# Sensor_v10.net
KiCad netlist of a schematic drawn in EAGLE
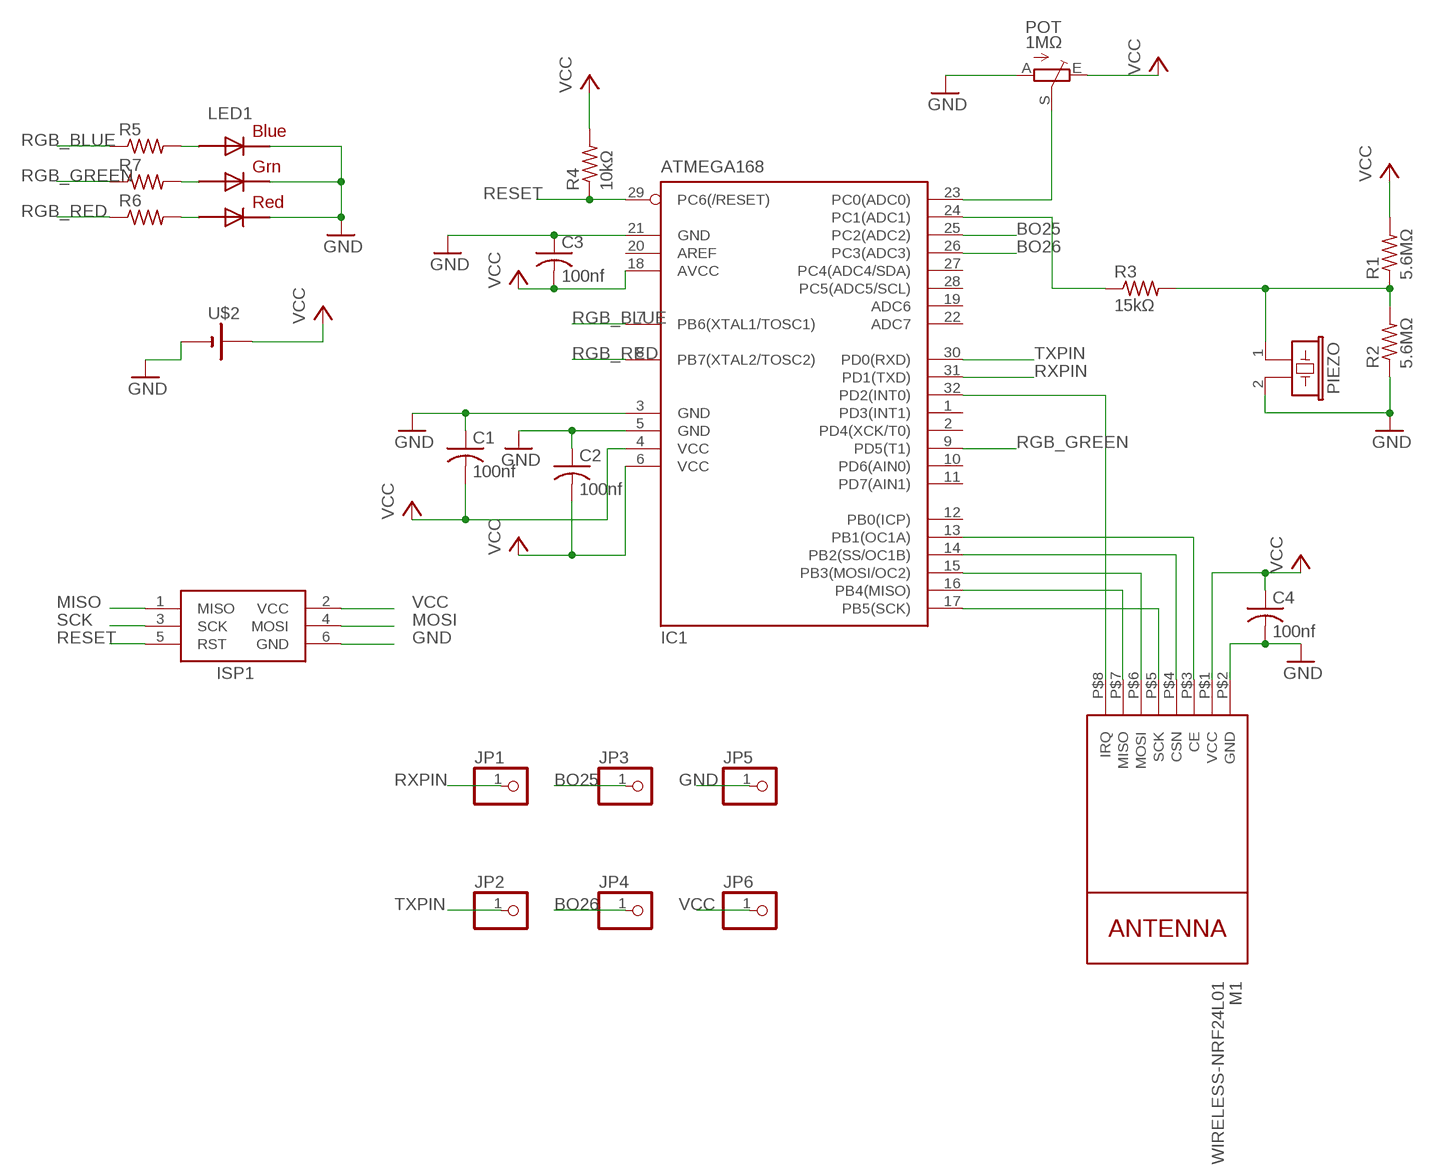
[diagram p0: schematic, sheet 1]

(export (version "E")
  (design (tool "Eeschema 10.0.6"))
  (components
    (comp (ref "C1")
      (value "100nf")
      (footprint "eagle-import:C0805")
      (libsource (lib "eagle-import") (part "resistor_C-USC0805"))
    )
    (comp (ref "C2")
      (value "100nf")
      (footprint "eagle-import:C0805")
      (libsource (lib "eagle-import") (part "C-USC0805"))
    )
    (comp (ref "C3")
      (value "100nf")
      (footprint "eagle-import:C0805")
      (libsource (lib "eagle-import") (part "resistor_C-USC0805"))
    )
    (comp (ref "C4")
      (value "100nf")
      (footprint "eagle-import:C0805")
      (libsource (lib "eagle-import") (part "C-USC0805"))
    )
    (comp (ref "IC1")
      (value "ATMEGA168")
      (footprint "eagle-import:TQFP32-08")
      (fields (field (name "MPN") "ATMEGA8-16AU"))
      (libsource (lib "eagle-import") (part "MEGA8-AI"))
    )
    (comp (ref "ISP1")
      (value "AVRISP-6")
      (footprint "eagle-import:AVRISP")
      (libsource (lib "eagle-import") (part "AVRISP-6"))
    )
    (comp (ref "JP1")
      (value "PINHD-1X1")
      (footprint "eagle-import:1X01")
      (libsource (lib "eagle-import") (part "PINHD-1X1"))
    )
    (comp (ref "JP2")
      (value "PINHD-1X1")
      (footprint "eagle-import:1X01")
      (libsource (lib "eagle-import") (part "PINHD-1X1"))
    )
    (comp (ref "JP3")
      (value "PINHD-1X1")
      (footprint "eagle-import:1X01")
      (libsource (lib "eagle-import") (part "PINHD-1X1"))
    )
    (comp (ref "JP4")
      (value "PINHD-1X1")
      (footprint "eagle-import:1X01")
      (libsource (lib "eagle-import") (part "PINHD-1X1"))
    )
    (comp (ref "JP5")
      (value "PINHD-1X1")
      (footprint "eagle-import:1X01")
      (libsource (lib "eagle-import") (part "PINHD-1X1"))
    )
    (comp (ref "JP6")
      (value "PINHD-1X1")
      (footprint "eagle-import:1X01")
      (libsource (lib "eagle-import") (part "PINHD-1X1"))
    )
    (comp (ref "LED1")
      (value "RGBLED5050")
      (footprint "eagle-import:RGBLED5050")
      (libsource (lib "eagle-import") (part "RGBLED5050"))
    )
    (comp (ref "M1")
      (value "WIRELESS-NRF24L01")
      (footprint "eagle-import:WIRELESS-NRF24L01")
      (libsource (lib "eagle-import") (part "WIRELESS-NRF24L01"))
    )
    (comp (ref "PIEZO")
      (value "EFBAA40D101")
      (footprint "eagle-import:EFBAA40D101")
      (libsource (lib "eagle-import") (part "EFB?AA40D101"))
    )
    (comp (ref "POT")
      (value "1MΩ")
      (footprint "eagle-import:CA6V")
      (libsource (lib "eagle-import") (part "TRIM_EU-CA6V"))
    )
    (comp (ref "R1")
      (value "5.6MΩ")
      (footprint "eagle-import:R0805")
      (libsource (lib "eagle-import") (part "R-US_R0805"))
    )
    (comp (ref "R2")
      (value "5.6MΩ")
      (footprint "eagle-import:R0805")
      (libsource (lib "eagle-import") (part "R-US_R0805"))
    )
    (comp (ref "R3")
      (value "15kΩ")
      (footprint "eagle-import:R0805")
      (libsource (lib "eagle-import") (part "R-US_R0805"))
    )
    (comp (ref "R4")
      (value "10kΩ")
      (footprint "eagle-import:R0805")
      (libsource (lib "eagle-import") (part "R-US_R0805"))
    )
    (comp (ref "R5")
      (value "R-US_R0805")
      (footprint "eagle-import:R0805")
      (libsource (lib "eagle-import") (part "R-US_R0805"))
    )
    (comp (ref "R6")
      (value "R-US_R0805")
      (footprint "eagle-import:R0805")
      (libsource (lib "eagle-import") (part "R-US_R0805"))
    )
    (comp (ref "R7")
      (value "R-US_R0805")
      (footprint "eagle-import:R0805")
      (libsource (lib "eagle-import") (part "R-US_R0805"))
    )
    (comp (ref "U$2")
      (value "CR2032SMT")
      (footprint "eagle-import:CR2032-SMD")
      (libsource (lib "eagle-import") (part "CR2032SMT"))
    )
  )
  (nets
    (net (code "1") (name "/BO25") (class "Default")
      (node (ref "IC1") (pin "25") (pinfunction "PC2(ADC2)_25") (pintype "bidirectional"))
      (node (ref "JP3") (pin "1") (pinfunction "1_1") (pintype "passive"))
    )
    (net (code "2") (name "/BO26") (class "Default")
      (node (ref "IC1") (pin "26") (pinfunction "PC3(ADC3)_26") (pintype "bidirectional"))
      (node (ref "JP4") (pin "1") (pinfunction "1_1") (pintype "passive"))
    )
    (net (code "3") (name "/MISO") (class "Default")
      (node (ref "IC1") (pin "16") (pinfunction "PB4(MISO)_16") (pintype "bidirectional"))
      (node (ref "ISP1") (pin "1") (pinfunction "MISO_1") (pintype "input"))
      (node (ref "M1") (pin "P$7") (pinfunction "MISO_P$7") (pintype "bidirectional"))
    )
    (net (code "4") (name "/MOSI") (class "Default")
      (node (ref "IC1") (pin "15") (pinfunction "PB3(MOSI/OC2)_15") (pintype "bidirectional"))
      (node (ref "ISP1") (pin "4") (pinfunction "MOSI_4") (pintype "output"))
      (node (ref "M1") (pin "P$6") (pinfunction "MOSI_P$6") (pintype "bidirectional"))
    )
    (net (code "5") (name "/RESET") (class "Default")
      (node (ref "IC1") (pin "29") (pinfunction "PC6(/RESET)_29") (pintype "bidirectional"))
      (node (ref "ISP1") (pin "5") (pinfunction "RST_5") (pintype "output"))
      (node (ref "R4") (pin "1") (pinfunction "1_1") (pintype "passive"))
    )
    (net (code "6") (name "/RGB_BLUE") (class "Default")
      (node (ref "IC1") (pin "7") (pinfunction "PB6(XTAL1/TOSC1)_7") (pintype "bidirectional"))
      (node (ref "R5") (pin "1") (pinfunction "1_1") (pintype "passive"))
    )
    (net (code "7") (name "/RGB_GREEN") (class "Default")
      (node (ref "IC1") (pin "9") (pinfunction "PD5(T1)_9") (pintype "bidirectional"))
      (node (ref "R7") (pin "1") (pinfunction "1_1") (pintype "passive"))
    )
    (net (code "8") (name "/RGB_RED") (class "Default")
      (node (ref "IC1") (pin "8") (pinfunction "PB7(XTAL2/TOSC2)_8") (pintype "bidirectional"))
      (node (ref "R6") (pin "1") (pinfunction "1_1") (pintype "passive"))
    )
    (net (code "9") (name "/RXPIN") (class "Default")
      (node (ref "IC1") (pin "31") (pinfunction "PD1(TXD)_31") (pintype "bidirectional"))
      (node (ref "JP1") (pin "1") (pinfunction "1_1") (pintype "passive"))
    )
    (net (code "10") (name "/SCK") (class "Default")
      (node (ref "IC1") (pin "17") (pinfunction "PB5(SCK)_17") (pintype "bidirectional"))
      (node (ref "ISP1") (pin "3") (pinfunction "SCK_3") (pintype "output"))
      (node (ref "M1") (pin "P$5") (pinfunction "SCK_P$5") (pintype "bidirectional"))
    )
    (net (code "11") (name "/TXPIN") (class "Default")
      (node (ref "IC1") (pin "30") (pinfunction "PD0(RXD)_30") (pintype "bidirectional"))
      (node (ref "JP2") (pin "1") (pinfunction "1_1") (pintype "passive"))
    )
    (net (code "12") (name "GND") (class "Default")
      (node (ref "C1") (pin "1") (pinfunction "1_1") (pintype "passive"))
      (node (ref "C2") (pin "1") (pinfunction "1_1") (pintype "passive"))
      (node (ref "C3") (pin "1") (pinfunction "1_1") (pintype "passive"))
      (node (ref "C4") (pin "2") (pinfunction "2_2") (pintype "passive"))
      (node (ref "IC1") (pin "21") (pinfunction "GND_21") (pintype "power_in"))
      (node (ref "IC1") (pin "3") (pinfunction "GND_3") (pintype "power_in"))
      (node (ref "IC1") (pin "5") (pinfunction "GND_5") (pintype "power_in"))
      (node (ref "ISP1") (pin "6") (pinfunction "GND_6") (pintype "power_in"))
      (node (ref "JP5") (pin "1") (pinfunction "1_1") (pintype "passive"))
      (node (ref "LED1") (pin "4") (pinfunction "BLUE_C_4") (pintype "bidirectional"))
      (node (ref "LED1") (pin "5") (pinfunction "RED_C_5") (pintype "bidirectional"))
      (node (ref "LED1") (pin "6") (pinfunction "GREEN_C_6") (pintype "bidirectional"))
      (node (ref "M1") (pin "P$2") (pinfunction "GND_P$2") (pintype "power_in"))
      (node (ref "PIEZO") (pin "2") (pinfunction "2_2") (pintype "passive"))
      (node (ref "POT") (pin "A") (pinfunction "A_A") (pintype "passive"))
      (node (ref "R2") (pin "1") (pinfunction "1_1") (pintype "passive"))
      (node (ref "U$2") (pin "-$1") (pinfunction "-_-$1") (pintype "passive"))
    )
    (net (code "13") (name "Net-(IC1-PB1(OC1A))") (class "Default")
      (node (ref "IC1") (pin "13") (pinfunction "PB1(OC1A)_13") (pintype "bidirectional"))
      (node (ref "M1") (pin "P$3") (pinfunction "CE_P$3") (pintype "bidirectional"))
    )
    (net (code "14") (name "Net-(IC1-PB2(SS{slash}OC1B))") (class "Default")
      (node (ref "IC1") (pin "14") (pinfunction "PB2(SS/OC1B)_14") (pintype "bidirectional"))
      (node (ref "M1") (pin "P$4") (pinfunction "CSN_P$4") (pintype "bidirectional"))
    )
    (net (code "15") (name "Net-(IC1-PC0(ADC0))") (class "Default")
      (node (ref "IC1") (pin "23") (pinfunction "PC0(ADC0)_23") (pintype "bidirectional"))
      (node (ref "POT") (pin "S") (pinfunction "S_S") (pintype "passive"))
    )
    (net (code "16") (name "Net-(IC1-PC1(ADC1))") (class "Default")
      (node (ref "IC1") (pin "24") (pinfunction "PC1(ADC1)_24") (pintype "bidirectional"))
      (node (ref "R3") (pin "1") (pinfunction "1_1") (pintype "passive"))
    )
    (net (code "17") (name "Net-(IC1-PD2(INT0))") (class "Default")
      (node (ref "IC1") (pin "32") (pinfunction "PD2(INT0)_32") (pintype "bidirectional"))
      (node (ref "M1") (pin "P$8") (pinfunction "IRQ_P$8") (pintype "bidirectional"))
    )
    (net (code "18") (name "Net-(LED1-BLUE_A)") (class "Default")
      (node (ref "LED1") (pin "3") (pinfunction "BLUE_A_3") (pintype "bidirectional"))
      (node (ref "R5") (pin "2") (pinfunction "2_2") (pintype "passive"))
    )
    (net (code "19") (name "Net-(LED1-GREEN_A)") (class "Default")
      (node (ref "LED1") (pin "1") (pinfunction "GREEN_A_1") (pintype "bidirectional"))
      (node (ref "R7") (pin "2") (pinfunction "2_2") (pintype "passive"))
    )
    (net (code "20") (name "Net-(LED1-RED_A)") (class "Default")
      (node (ref "LED1") (pin "2") (pinfunction "RED_A_2") (pintype "bidirectional"))
      (node (ref "R6") (pin "2") (pinfunction "2_2") (pintype "passive"))
    )
    (net (code "21") (name "Net-(PIEZO-Pad1)") (class "Default")
      (node (ref "PIEZO") (pin "1") (pinfunction "1_1") (pintype "passive"))
      (node (ref "R1") (pin "1") (pinfunction "1_1") (pintype "passive"))
      (node (ref "R2") (pin "2") (pinfunction "2_2") (pintype "passive"))
      (node (ref "R3") (pin "2") (pinfunction "2_2") (pintype "passive"))
    )
    (net (code "22") (name "VCC") (class "Default")
      (node (ref "C1") (pin "2") (pinfunction "2_2") (pintype "passive"))
      (node (ref "C2") (pin "2") (pinfunction "2_2") (pintype "passive"))
      (node (ref "C3") (pin "2") (pinfunction "2_2") (pintype "passive"))
      (node (ref "C4") (pin "1") (pinfunction "1_1") (pintype "passive"))
      (node (ref "IC1") (pin "18") (pinfunction "AVCC_18") (pintype "power_in"))
      (node (ref "IC1") (pin "4") (pinfunction "VCC_4") (pintype "power_in"))
      (node (ref "IC1") (pin "6") (pinfunction "VCC_6") (pintype "power_in"))
      (node (ref "ISP1") (pin "2") (pinfunction "VCC_2") (pintype "power_in"))
      (node (ref "JP6") (pin "1") (pinfunction "1_1") (pintype "passive"))
      (node (ref "M1") (pin "P$1") (pinfunction "VCC_P$1") (pintype "power_in"))
      (node (ref "POT") (pin "E") (pinfunction "E_E") (pintype "passive"))
      (node (ref "R1") (pin "2") (pinfunction "2_2") (pintype "passive"))
      (node (ref "R4") (pin "2") (pinfunction "2_2") (pintype "passive"))
      (node (ref "U$2") (pin "+$1") (pinfunction "+1_+$1") (pintype "passive"))
    )
    (net (code "23") (name "unconnected-(IC1-ADC6-Pad19)") (class "Default")
      (node (ref "IC1") (pin "19") (pinfunction "ADC6_19") (pintype "bidirectional"))
    )
    (net (code "24") (name "unconnected-(IC1-ADC7-Pad22)") (class "Default")
      (node (ref "IC1") (pin "22") (pinfunction "ADC7_22") (pintype "bidirectional"))
    )
    (net (code "25") (name "unconnected-(IC1-AREF-Pad20)") (class "Default")
      (node (ref "IC1") (pin "20") (pinfunction "AREF_20") (pintype "passive"))
    )
    (net (code "26") (name "unconnected-(IC1-PB0(ICP)-Pad12)") (class "Default")
      (node (ref "IC1") (pin "12") (pinfunction "PB0(ICP)_12") (pintype "bidirectional"))
    )
    (net (code "27") (name "unconnected-(IC1-PC4(ADC4{slash}SDA)-Pad27)") (class "Default")
      (node (ref "IC1") (pin "27") (pinfunction "PC4(ADC4/SDA)_27") (pintype "bidirectional"))
    )
    (net (code "28") (name "unconnected-(IC1-PC5(ADC5{slash}SCL)-Pad28)") (class "Default")
      (node (ref "IC1") (pin "28") (pinfunction "PC5(ADC5/SCL)_28") (pintype "bidirectional"))
    )
    (net (code "29") (name "unconnected-(IC1-PD3(INT1)-Pad1)") (class "Default")
      (node (ref "IC1") (pin "1") (pinfunction "PD3(INT1)_1") (pintype "bidirectional"))
    )
    (net (code "30") (name "unconnected-(IC1-PD4(XCK{slash}T0)-Pad2)") (class "Default")
      (node (ref "IC1") (pin "2") (pinfunction "PD4(XCK/T0)_2") (pintype "bidirectional"))
    )
    (net (code "31") (name "unconnected-(IC1-PD6(AIN0)-Pad10)") (class "Default")
      (node (ref "IC1") (pin "10") (pinfunction "PD6(AIN0)_10") (pintype "bidirectional"))
    )
    (net (code "32") (name "unconnected-(IC1-PD7(AIN1)-Pad11)") (class "Default")
      (node (ref "IC1") (pin "11") (pinfunction "PD7(AIN1)_11") (pintype "bidirectional"))
    )
  )
)
